# Power.net
KiCad netlist of a schematic drawn in Altium Designer
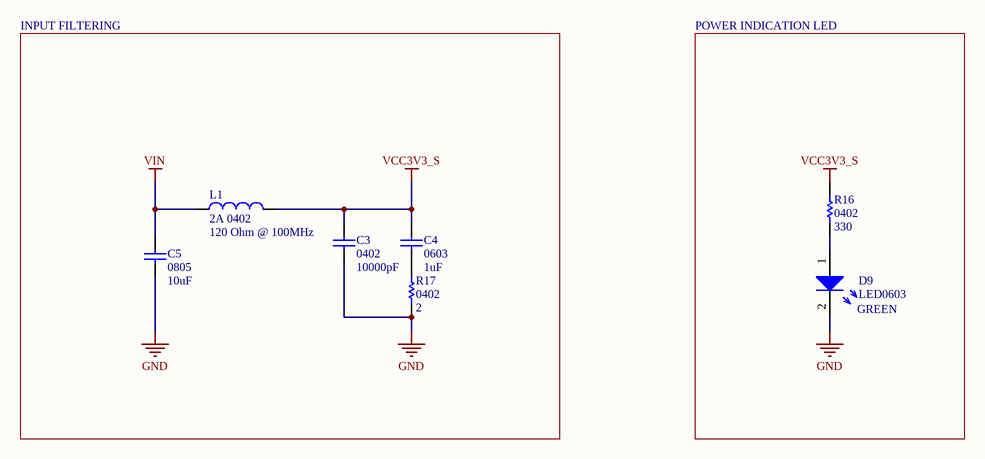
[diagram p0: Power.SchDoc]

(export (version "E")
  (design (tool "Eeschema 10.0.6"))
  (components
    (comp (ref "C3")
      (value "0402")
      (footprint "CAP0402R")
      (description "0402 capacitor")
      (fields
        (field (name "ALTIUM_VALUE") "10000pF")
        (field (name "MANUFACTURER") "Murata")
        (field (name "MANUFACTURER PART NUMBER") "GCM155R71H103KA55D")
      )
      (libsource (lib "heron-general") (part "CAP0402"))
    )
    (comp (ref "C4")
      (value "0603")
      (footprint "CAP0603R")
      (description "0603 capacitor")
      (fields
        (field (name "ALTIUM_VALUE") "1uF")
        (field (name "MANUFACTURER") "KEMET")
        (field (name "MANUFACTURER PART NUMBER") "C0603C105K4RACAUTO")
      )
      (libsource (lib "heron-general") (part "CAP0603"))
    )
    (comp (ref "C5")
      (value "0805")
      (footprint "CAP0805R")
      (description "0805 capacitor")
      (fields
        (field (name "ALTIUM_VALUE") "10uF")
        (field (name "MANUFACTURER") "Murata")
        (field (name "MANUFACTURER PART NUMBER") "GCM21BR70J106KE22K")
      )
      (libsource (lib "heron-general") (part "CAP0805"))
    )
    (comp (ref "D9")
      (value "LED0603")
      (footprint "LED0603")
      (description "Generic 0603 LED. Use ChipLED from Osram for generic ones.")
      (fields
        (field (name "COLOUR") "GREEN")
        (field (name "MANUFACTURER") "Osram Opto")
        (field (name "MANUFACTURER PART NUMBER") "LTQ39G-Q1OO-25-1")
      )
      (libsource (lib "heron-general") (part "LED0603"))
    )
    (comp (ref "L1")
      (value "2A 0402")
      (footprint "RES0402R")
      (description "Inductor")
      (fields
        (field (name "ALTIUM_VALUE") "120 Ohm @ 100MHz")
        (field (name "MANUFACTURER") "Murata")
        (field (name "MANUFACTURER PART NUMBER") "BLM15PX121SZ1D")
        (field (name "PUBLISHER") "Altium Limited")
      )
      (libsource (lib "Miscellaneous Devices") (part "Inductor"))
    )
    (comp (ref "R16")
      (value "0402")
      (footprint "RES0402R")
      (description "0402 resistor")
      (fields
        (field (name "ALTIUM_VALUE") "330")
        (field (name "MANUFACTURER") "TE Connectivity")
        (field (name "MANUFACTURER PART NUMBER") "CRGCQ0402F330R")
      )
      (libsource (lib "heron-general") (part "RES0402"))
    )
    (comp (ref "R17")
      (value "0402")
      (footprint "RES0402R")
      (description "0402 resistor")
      (fields
        (field (name "ALTIUM_VALUE") "2")
        (field (name "MANUFACTURER") "Yageo")
        (field (name "MANUFACTURER PART NUMBER") "AC0402FR-072RL")
      )
      (libsource (lib "heron-general") (part "RES0402"))
    )
  )
  (nets
    (net (code "1") (name "GND") (class "Default")
      (node (ref "C3") (pin "1") (pinfunction "1_1") (pintype "passive"))
      (node (ref "C5") (pin "1") (pinfunction "1_1") (pintype "passive"))
      (node (ref "D9") (pin "2") (pinfunction "2_2") (pintype "passive"))
      (node (ref "R17") (pin "1") (pinfunction "1_1") (pintype "passive"))
    )
    (net (code "2") (name "Net-(C4-Pad1)") (class "Default")
      (node (ref "C4") (pin "1") (pinfunction "1_1") (pintype "passive"))
      (node (ref "R17") (pin "2") (pinfunction "2_2") (pintype "passive"))
    )
    (net (code "3") (name "Net-(D9-Pad1)") (class "Default")
      (node (ref "D9") (pin "1") (pinfunction "1_1") (pintype "passive"))
      (node (ref "R16") (pin "1") (pinfunction "1_1") (pintype "passive"))
    )
    (net (code "4") (name "VCC3V3_S") (class "Default")
      (node (ref "C3") (pin "2") (pinfunction "2_2") (pintype "passive"))
      (node (ref "C4") (pin "2") (pinfunction "2_2") (pintype "passive"))
      (node (ref "L1") (pin "2") (pinfunction "2_2") (pintype "passive"))
      (node (ref "R16") (pin "2") (pinfunction "2_2") (pintype "passive"))
    )
    (net (code "5") (name "VIN") (class "Default")
      (node (ref "C5") (pin "2") (pinfunction "2_2") (pintype "passive"))
      (node (ref "L1") (pin "1") (pinfunction "1_1") (pintype "passive"))
    )
  )
)
